# Main.net
KiCad netlist of a schematic drawn in Altium Designer
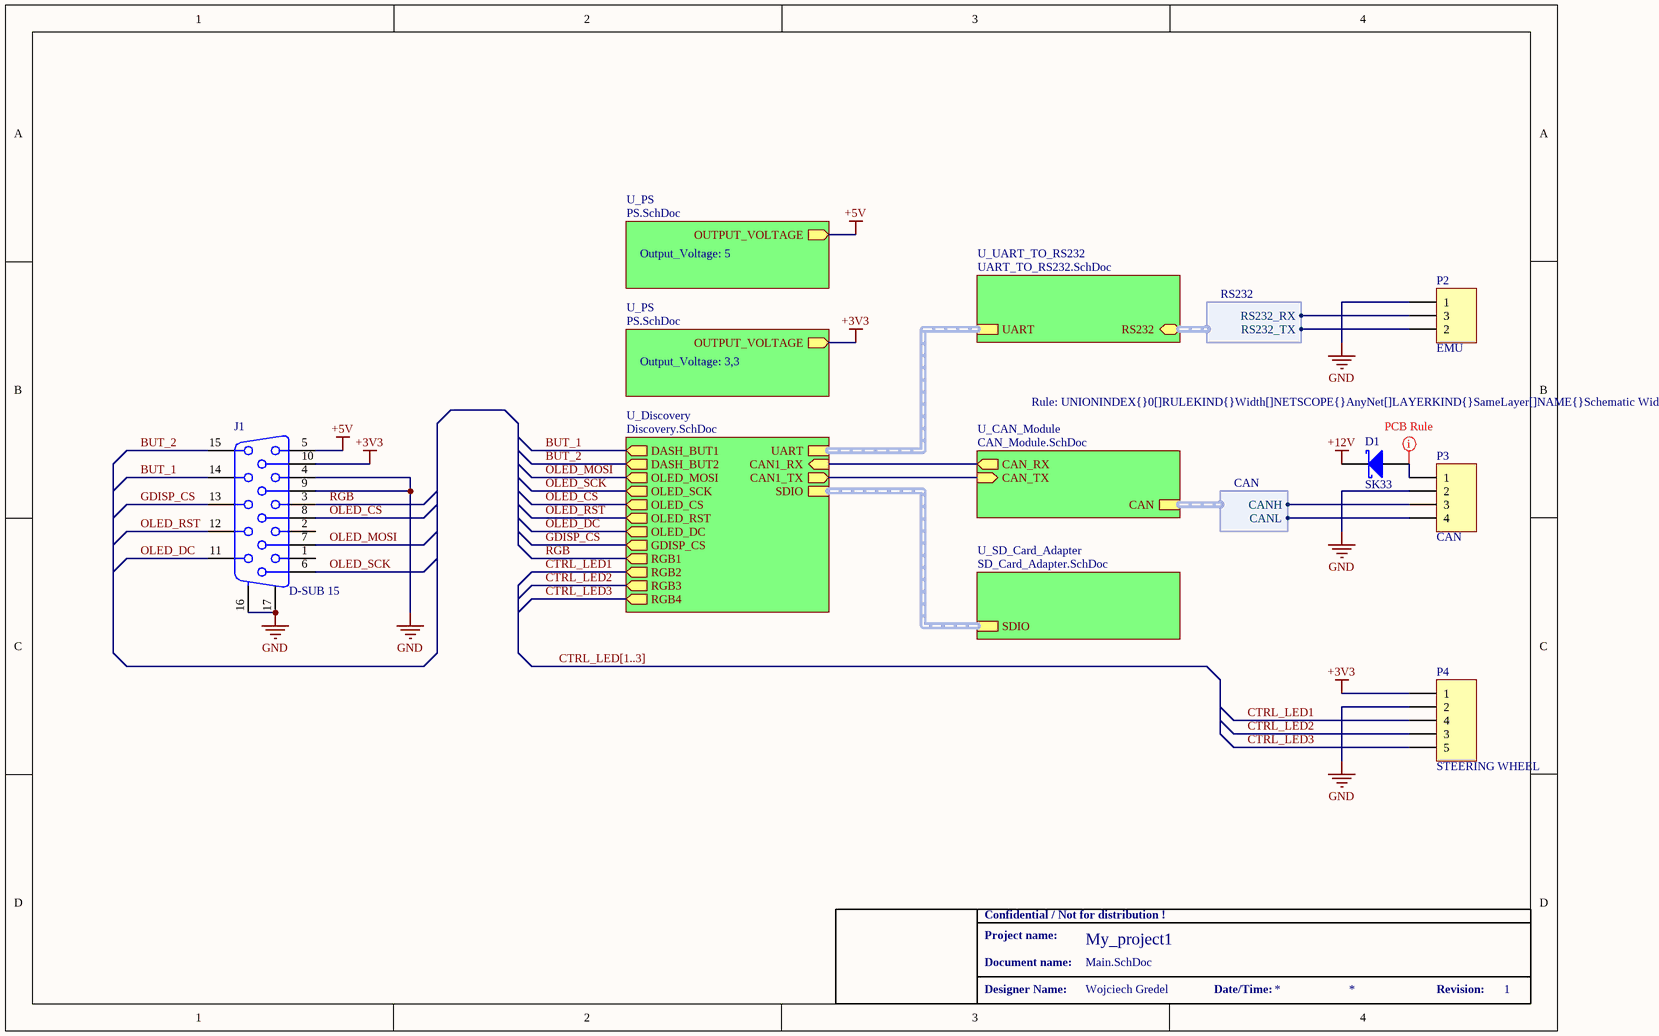
[diagram p0: Main.SchDoc]

(export (version "E")
  (design (tool "Eeschema 10.0.6"))
  (components
    (comp (ref "D1")
      (value "SK33")
      (footprint "DO214AB_IPC_MD")
      (description "Schottky Diode")
      (fields (field (name "MANUFACTURER") "Diotec"))
      (libsource (lib "DataLogger") (part "SK33"))
    )
    (comp (ref "J1")
      (value "D-SUB 15")
      (footprint "Dsub-3H15")
      (description "Receptacle Assembly, 15-Pin, Sim Line Connector")
      (fields (field (name "MANUFACTURER") "TE Connectivity") (field (name "PUBLISHER") "Altium Limited"))
      (libsource (lib "Dashboard") (part "D-SUB 15"))
    )
    (comp (ref "P2")
      (value "EMU")
      (footprint "HDR_1x3_3_94_LOCKING")
      (description "ST1212 3 pin waterproof connector")
      (fields (field (name "MANUFACTURER") "Joint Tech") (field (name "PUBLISHER") "Altium Limited"))
      (libsource (lib "DataLogger") (part "MHDR1X3"))
    )
    (comp (ref "P3")
      (value "CAN")
      (footprint "HDR_1x4_3_94_LOCKING")
      (description "Header, 4-Pin")
      (fields (field (name "MANUFACTURER") "Joint Tech") (field (name "PUBLISHER") "Altium Limited"))
      (libsource (lib "DataLogger") (part "Header 4"))
    )
    (comp (ref "P4")
      (value "STEERING WHEEL")
      (footprint "HDR_1x5_3_94_LOCKING")
      (description "Header, 5-Pin")
      (fields (field (name "MANUFACTURER") "Joint Tech") (field (name "PUBLISHER") "Altium Limited"))
      (libsource (lib "DataLogger") (part "Header 5"))
    )
  )
  (nets
    (net (code "3") (name "+3V3") (class "Default")
      (node (ref "J1") (pin "10") (pinfunction "10_10") (pintype "passive"))
      (node (ref "P4") (pin "1") (pinfunction "1_1") (pintype "passive"))
    )
    (net (code "4") (name "+5V") (class "Default")
      (node (ref "J1") (pin "5") (pinfunction "5_5") (pintype "passive"))
    )
    (net (code "5") (name "+12V") (class "Default")
      (node (ref "D1") (pin "2") (pinfunction "K_2") (pintype "passive"))
    )
    (net (code "6") (name "/BUT_1") (class "Default")
      (node (ref "J1") (pin "14") (pinfunction "14_14") (pintype "passive"))
    )
    (net (code "7") (name "/BUT_2") (class "Default")
      (node (ref "J1") (pin "15") (pinfunction "15_15") (pintype "passive"))
    )
    (net (code "9") (name "/CANH") (class "Default")
      (node (ref "P3") (pin "3") (pinfunction "3_3") (pintype "passive"))
    )
    (net (code "10") (name "/CANL") (class "Default")
      (node (ref "P3") (pin "4") (pinfunction "4_4") (pintype "passive"))
    )
    (net (code "12") (name "/CTRL_LED1") (class "Default")
      (node (ref "P4") (pin "4") (pinfunction "4_4") (pintype "passive"))
    )
    (net (code "13") (name "/CTRL_LED2") (class "Default")
      (node (ref "P4") (pin "3") (pinfunction "3_3") (pintype "passive"))
    )
    (net (code "14") (name "/CTRL_LED3") (class "Default")
      (node (ref "P4") (pin "5") (pinfunction "5_5") (pintype "passive"))
    )
    (net (code "16") (name "/GDISP_CS") (class "Default")
      (node (ref "J1") (pin "13") (pinfunction "13_13") (pintype "passive"))
    )
    (net (code "17") (name "/OLED_CS") (class "Default")
      (node (ref "J1") (pin "8") (pinfunction "8_8") (pintype "passive"))
    )
    (net (code "18") (name "/OLED_DC") (class "Default")
      (node (ref "J1") (pin "11") (pinfunction "11_11") (pintype "passive"))
    )
    (net (code "19") (name "/OLED_MOSI") (class "Default")
      (node (ref "J1") (pin "7") (pinfunction "7_7") (pintype "passive"))
    )
    (net (code "20") (name "/OLED_RST") (class "Default")
      (node (ref "J1") (pin "12") (pinfunction "12_12") (pintype "passive"))
    )
    (net (code "21") (name "/OLED_SCK") (class "Default")
      (node (ref "J1") (pin "6") (pinfunction "6_6") (pintype "passive"))
    )
    (net (code "22") (name "/RGB") (class "Default")
      (node (ref "J1") (pin "3") (pinfunction "3_3") (pintype "passive"))
    )
    (net (code "23") (name "/RS232_RX") (class "Default")
      (node (ref "P2") (pin "3") (pinfunction "3_3") (pintype "passive"))
    )
    (net (code "24") (name "/RS232_TX") (class "Default")
      (node (ref "P2") (pin "2") (pinfunction "2_2") (pintype "passive"))
    )
    (net (code "29") (name "GND") (class "Default")
      (node (ref "J1") (pin "16") (pinfunction "MH1_16") (pintype "passive"))
      (node (ref "J1") (pin "17") (pinfunction "MH2_17") (pintype "passive"))
      (node (ref "J1") (pin "4") (pinfunction "4_4") (pintype "passive"))
      (node (ref "J1") (pin "9") (pinfunction "9_9") (pintype "passive"))
      (node (ref "P2") (pin "1") (pinfunction "1_1") (pintype "passive"))
      (node (ref "P3") (pin "2") (pinfunction "2_2") (pintype "passive"))
      (node (ref "P4") (pin "2") (pinfunction "2_2") (pintype "passive"))
    )
    (net (code "30") (name "Net-(D1-A)") (class "Default")
      (node (ref "D1") (pin "1") (pinfunction "A_1") (pintype "passive"))
      (node (ref "P3") (pin "1") (pinfunction "1_1") (pintype "passive"))
    )
    (net (code "31") (name "unconnected-(J1-Pad1)") (class "Default")
      (node (ref "J1") (pin "1") (pinfunction "1_1") (pintype "passive"))
    )
    (net (code "32") (name "unconnected-(J1-Pad2)") (class "Default")
      (node (ref "J1") (pin "2") (pinfunction "2_2") (pintype "passive"))
    )
  )
)
